# Amplifier.net
KiCad netlist of a schematic drawn in Altium Designer
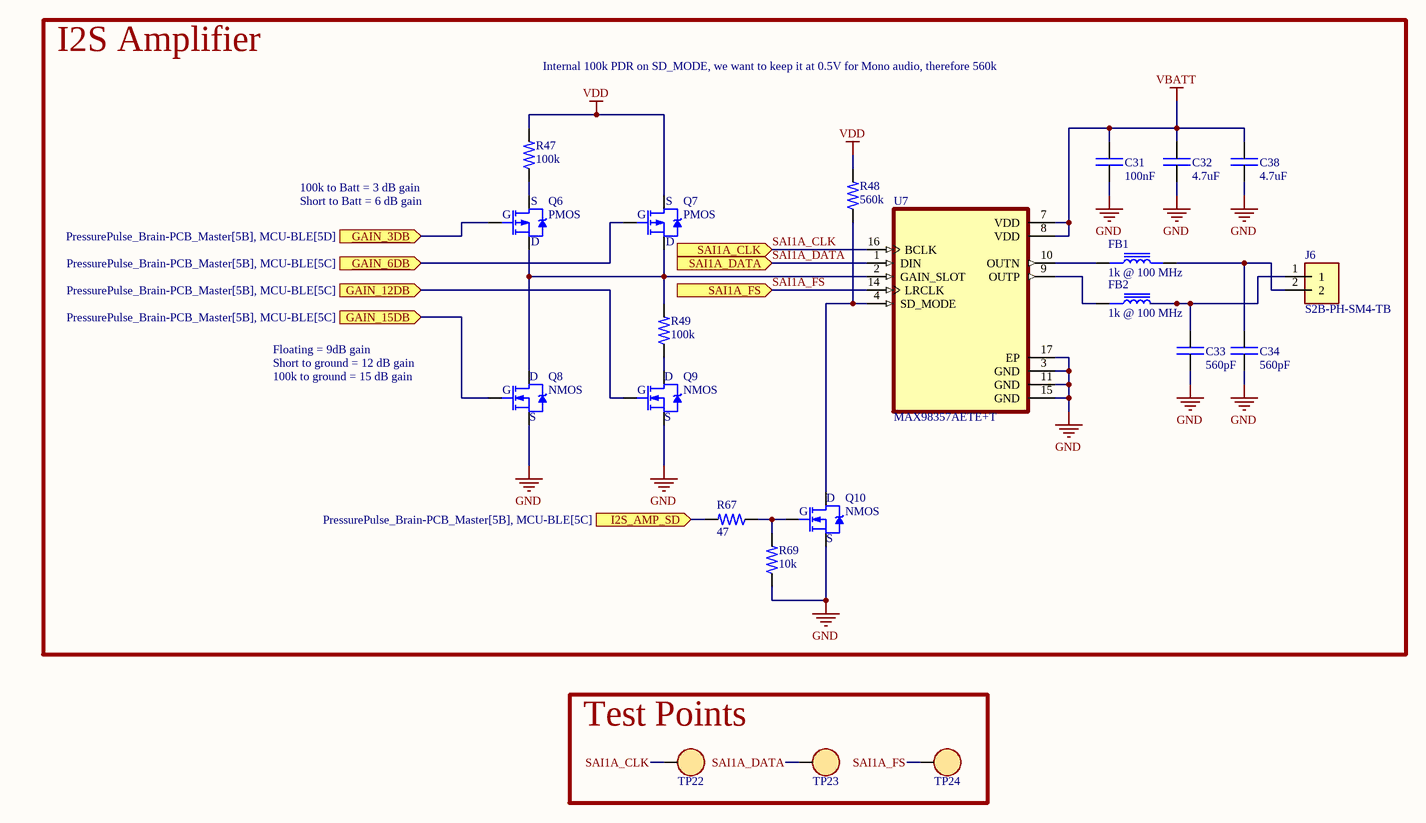
[diagram p0: Amplifier.SchDoc]

(export (version "E")
  (design (tool "Eeschema 10.0.6"))
  (components
    (comp (ref "C31")
      (value "100nF")
      (footprint "PressurePulse:0402C")
      (description "Capacitor")
      (fields (field (name "Comment") "CAP"))
      (libsource (lib "PressurePulse") (part "CAP"))
    )
    (comp (ref "C32")
      (value "4.7uF")
      (footprint "PressurePulse:0402C")
      (description "Capacitor")
      (fields (field (name "Comment") "CAP"))
      (libsource (lib "PressurePulse") (part "CAP"))
    )
    (comp (ref "C33")
      (value "560pF")
      (footprint "PressurePulse:0402C")
      (description "Capacitor")
      (fields (field (name "Comment") "CAP"))
      (libsource (lib "PressurePulse") (part "CAP"))
    )
    (comp (ref "C34")
      (value "560pF")
      (footprint "PressurePulse:0402C")
      (description "Capacitor")
      (fields (field (name "Comment") "CAP"))
      (libsource (lib "PressurePulse") (part "CAP"))
    )
    (comp (ref "C38")
      (value "4.7uF")
      (footprint "PressurePulse:0402C")
      (description "Capacitor")
      (fields (field (name "Comment") "CAP"))
      (libsource (lib "PressurePulse") (part "CAP"))
    )
    (comp (ref "FB1")
      (value "1k @ 100 MHz")
      (footprint "PressurePulse:0603L")
      (fields (field (name "MFR") "TDK"))
      (libsource (lib "PressurePulse") (part "FERRITE BEAD"))
    )
    (comp (ref "FB2")
      (value "1k @ 100 MHz")
      (footprint "PressurePulse:0603L")
      (fields (field (name "MFR") "TDK"))
      (libsource (lib "PressurePulse") (part "FERRITE BEAD"))
    )
    (comp (ref "J6")
      (value "S2B-PH-SM4-TB")
      (footprint "PressurePulse:JST_PH-2POS-SMT-RA")
      (description "Connector Header Surface Mount, Right Angle 2 position 0.079 (2.00mm)")
      (fields (field (name "MFR") "JST Sales"))
      (libsource (lib "PressurePulse") (part "JST CONN 2POS PH"))
    )
    (comp (ref "Q6")
      (value "PMOS")
      (footprint "PressurePulse:SOT-23")
      (description "P-Channel MOSFET")
      (fields (field (name "MFR") "Diodes Incorporated"))
      (libsource (lib "PressurePulse") (part "PMOS"))
    )
    (comp (ref "Q7")
      (value "PMOS")
      (footprint "PressurePulse:SOT-23")
      (description "P-Channel MOSFET")
      (fields (field (name "MFR") "Diodes Incorporated"))
      (libsource (lib "PressurePulse") (part "PMOS"))
    )
    (comp (ref "Q8")
      (value "NMOS")
      (footprint "PressurePulse:SOT-23")
      (description "100V 1.6A 1.3W 220mΩ@10V,1.6A N Channel SOT-23  MOSFETs ROHS")
      (fields (field (name "MFR") "Infineon"))
      (libsource (lib "PressurePulse") (part "NMOS"))
    )
    (comp (ref "Q9")
      (value "NMOS")
      (footprint "PressurePulse:SOT-23")
      (description "100V 1.6A 1.3W 220mΩ@10V,1.6A N Channel SOT-23  MOSFETs ROHS")
      (fields (field (name "MFR") "Infineon"))
      (libsource (lib "PressurePulse") (part "NMOS"))
    )
    (comp (ref "Q10")
      (value "NMOS")
      (footprint "PressurePulse:SOT-23")
      (description "100V 1.6A 1.3W 220mΩ@10V,1.6A N Channel SOT-23  MOSFETs ROHS")
      (fields (field (name "MFR") "Infineon"))
      (libsource (lib "PressurePulse") (part "NMOS"))
    )
    (comp (ref "R47")
      (value "100k")
      (footprint "PressurePulse:0402R")
      (description "Resistor")
      (fields (field (name "Comment") "RES"))
      (libsource (lib "PressurePulse") (part "RES"))
    )
    (comp (ref "R48")
      (value "560k")
      (footprint "PressurePulse:0402R")
      (description "Resistor")
      (fields (field (name "Comment") "RES"))
      (libsource (lib "PressurePulse") (part "RES"))
    )
    (comp (ref "R49")
      (value "100k")
      (footprint "PressurePulse:0402R")
      (description "Resistor")
      (fields (field (name "Comment") "RES"))
      (libsource (lib "PressurePulse") (part "RES"))
    )
    (comp (ref "R67")
      (value "47")
      (footprint "PressurePulse:0402R")
      (description "Resistor")
      (fields (field (name "Comment") "RES"))
      (libsource (lib "PressurePulse") (part "RES"))
    )
    (comp (ref "R69")
      (value "10k")
      (footprint "PressurePulse:0402R")
      (description "Resistor")
      (fields (field (name "Comment") "RES"))
      (libsource (lib "PressurePulse") (part "RES"))
    )
    (comp (ref "TP22")
      (value "RH-5019")
      (footprint "PressurePulse:TP - RH-5019")
      (fields (field (name "MFR") "ronghe"))
      (libsource (lib "PressurePulse") (part "TEST POINT"))
    )
    (comp (ref "TP23")
      (value "RH-5019")
      (footprint "PressurePulse:TP - RH-5019")
      (fields (field (name "MFR") "ronghe"))
      (libsource (lib "PressurePulse") (part "TEST POINT"))
    )
    (comp (ref "TP24")
      (value "RH-5019")
      (footprint "PressurePulse:TP - RH-5019")
      (fields (field (name "MFR") "ronghe"))
      (libsource (lib "PressurePulse") (part "TEST POINT"))
    )
    (comp (ref "U7")
      (value "MAX98357AETE+T")
      (footprint "PressurePulse:16-WFQFN EXPOSED PAD")
      (description "I2S Audio DAC and amp")
      (fields (field (name "MFR") "Analog Devices"))
      (libsource (lib "PressurePulse") (part "MAX98357AETE+T"))
    )
  )
  (nets
    (net (code "1") (name "/GAIN_3DB") (class "Default")
      (node (ref "Q6") (pin "G") (pinfunction "G_G") (pintype "passive"))
    )
    (net (code "2") (name "/GAIN_6DB") (class "Default")
      (node (ref "Q7") (pin "G") (pinfunction "G_G") (pintype "passive"))
    )
    (net (code "3") (name "/GAIN_12DB") (class "Default")
      (node (ref "Q9") (pin "G") (pinfunction "G_G") (pintype "passive"))
    )
    (net (code "4") (name "/GAIN_15DB") (class "Default")
      (node (ref "Q8") (pin "G") (pinfunction "G_G") (pintype "passive"))
    )
    (net (code "5") (name "/I2S_AMP_SD") (class "Default")
      (node (ref "R67") (pin "2") (pinfunction "2_2") (pintype "passive"))
    )
    (net (code "6") (name "/SAI1A_CLK") (class "Default")
      (node (ref "TP22") (pin "1") (pinfunction "1_1") (pintype "passive"))
      (node (ref "U7") (pin "16") (pinfunction "BCLK_16") (pintype "input"))
    )
    (net (code "7") (name "/SAI1A_DATA") (class "Default")
      (node (ref "TP23") (pin "1") (pinfunction "1_1") (pintype "passive"))
      (node (ref "U7") (pin "1") (pinfunction "DIN_1") (pintype "input"))
    )
    (net (code "8") (name "/SAI1A_FS") (class "Default")
      (node (ref "TP24") (pin "1") (pinfunction "1_1") (pintype "passive"))
      (node (ref "U7") (pin "14") (pinfunction "LRCLK_14") (pintype "input"))
    )
    (net (code "9") (name "GND") (class "Default")
      (node (ref "C31") (pin "2") (pinfunction "2_2") (pintype "passive"))
      (node (ref "C32") (pin "1") (pinfunction "1_1") (pintype "passive"))
      (node (ref "C33") (pin "1") (pinfunction "1_1") (pintype "passive"))
      (node (ref "C34") (pin "1") (pinfunction "1_1") (pintype "passive"))
      (node (ref "C38") (pin "1") (pinfunction "1_1") (pintype "passive"))
      (node (ref "Q10") (pin "S") (pinfunction "S_S") (pintype "passive"))
      (node (ref "Q8") (pin "S") (pinfunction "S_S") (pintype "passive"))
      (node (ref "Q9") (pin "S") (pinfunction "S_S") (pintype "passive"))
      (node (ref "R69") (pin "1") (pinfunction "1_1") (pintype "passive"))
      (node (ref "U7") (pin "11") (pinfunction "GND_11") (pintype "power_in"))
      (node (ref "U7") (pin "15") (pinfunction "GND_15") (pintype "power_in"))
      (node (ref "U7") (pin "17") (pinfunction "EP_17") (pintype "power_in"))
      (node (ref "U7") (pin "3") (pinfunction "GND_3") (pintype "power_in"))
    )
    (net (code "10") (name "Net-(C33-Pad2)") (class "Default")
      (node (ref "C33") (pin "2") (pinfunction "2_2") (pintype "passive"))
      (node (ref "FB2") (pin "2") (pinfunction "2_2") (pintype "passive"))
      (node (ref "J6") (pin "1") (pinfunction "1_1") (pintype "passive"))
    )
    (net (code "11") (name "Net-(C34-Pad2)") (class "Default")
      (node (ref "C34") (pin "2") (pinfunction "2_2") (pintype "passive"))
      (node (ref "FB1") (pin "2") (pinfunction "2_2") (pintype "passive"))
      (node (ref "J6") (pin "2") (pinfunction "2_2") (pintype "passive"))
    )
    (net (code "12") (name "Net-(Q6-PadS)") (class "Default")
      (node (ref "Q6") (pin "S") (pinfunction "S_S") (pintype "passive"))
      (node (ref "R47") (pin "1") (pinfunction "1_1") (pintype "passive"))
    )
    (net (code "13") (name "Net-(Q9-PadD)") (class "Default")
      (node (ref "Q9") (pin "D") (pinfunction "D_D") (pintype "passive"))
      (node (ref "R49") (pin "1") (pinfunction "1_1") (pintype "passive"))
    )
    (net (code "14") (name "Net-(Q10-PadG)") (class "Default")
      (node (ref "Q10") (pin "G") (pinfunction "G_G") (pintype "passive"))
      (node (ref "R67") (pin "1") (pinfunction "1_1") (pintype "passive"))
      (node (ref "R69") (pin "2") (pinfunction "2_2") (pintype "passive"))
    )
    (net (code "15") (name "Net-(U7-GAIN_SLOT)") (class "Default")
      (node (ref "Q6") (pin "D") (pinfunction "D_D") (pintype "passive"))
      (node (ref "Q7") (pin "D") (pinfunction "D_D") (pintype "passive"))
      (node (ref "Q8") (pin "D") (pinfunction "D_D") (pintype "passive"))
      (node (ref "R49") (pin "2") (pinfunction "2_2") (pintype "passive"))
      (node (ref "U7") (pin "2") (pinfunction "GAIN_SLOT_2") (pintype "input"))
    )
    (net (code "16") (name "Net-(U7-OUTN)") (class "Default")
      (node (ref "FB1") (pin "1") (pinfunction "1_1") (pintype "passive"))
      (node (ref "U7") (pin "10") (pinfunction "OUTN_10") (pintype "output"))
    )
    (net (code "17") (name "Net-(U7-OUTP)") (class "Default")
      (node (ref "FB2") (pin "1") (pinfunction "1_1") (pintype "passive"))
      (node (ref "U7") (pin "9") (pinfunction "OUTP_9") (pintype "output"))
    )
    (net (code "18") (name "Net-(U7-SD_MODE)") (class "Default")
      (node (ref "Q10") (pin "D") (pinfunction "D_D") (pintype "passive"))
      (node (ref "R48") (pin "1") (pinfunction "1_1") (pintype "passive"))
      (node (ref "U7") (pin "4") (pinfunction "SD_MODE_4") (pintype "input"))
    )
    (net (code "19") (name "VBATT") (class "Default")
      (node (ref "C31") (pin "1") (pinfunction "1_1") (pintype "passive"))
      (node (ref "C32") (pin "2") (pinfunction "2_2") (pintype "passive"))
      (node (ref "C38") (pin "2") (pinfunction "2_2") (pintype "passive"))
      (node (ref "U7") (pin "7") (pinfunction "VDD_7") (pintype "power_in"))
      (node (ref "U7") (pin "8") (pinfunction "VDD_8") (pintype "power_in"))
    )
    (net (code "20") (name "VDD") (class "Default")
      (node (ref "Q7") (pin "S") (pinfunction "S_S") (pintype "passive"))
      (node (ref "R47") (pin "2") (pinfunction "2_2") (pintype "passive"))
      (node (ref "R48") (pin "2") (pinfunction "2_2") (pintype "passive"))
    )
  )
)
